# Topsheet.net
KiCad netlist of a schematic drawn in Altium Designer
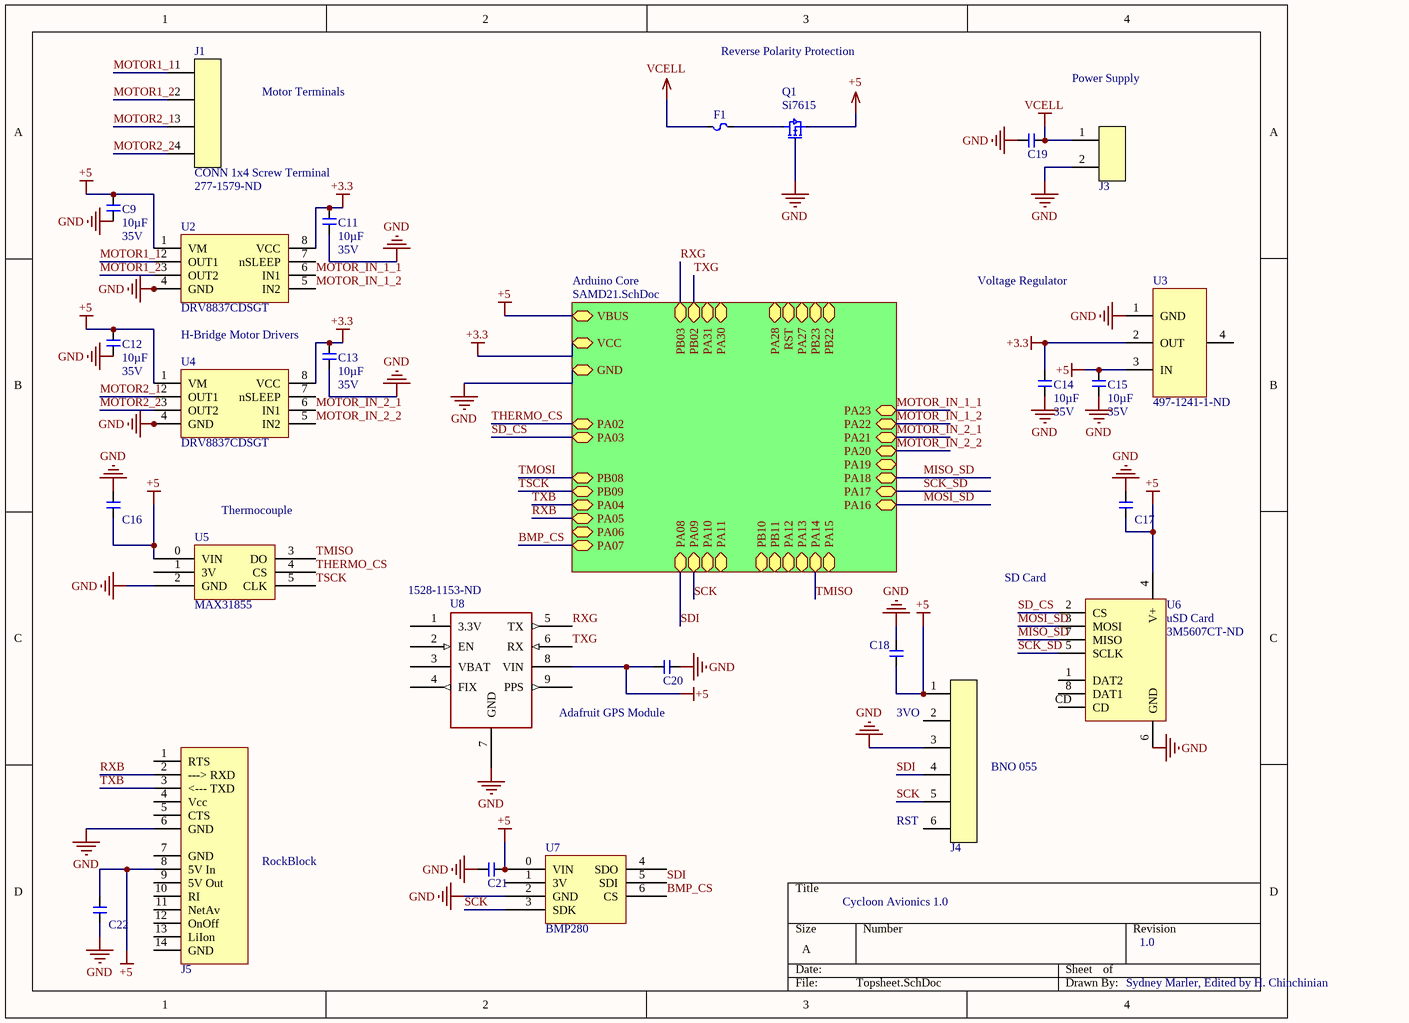
[diagram p0: Topsheet.SchDoc]

(export (version "E")
  (design (tool "Eeschema 10.0.6"))
  (components
    (comp (ref "C9")
      (value "__template_cap")
      (footprint "C0603")
      (description "CAP CER 10UF 35V X5R 0603 20%")
      (fields
        (field (name "CAPACITANCE (SHORTHAND)") "10µF")
        (field (name "RATED VOLTAGE") "35V")
        (field (name "MANUFACTURER") "Murata Electronics North America")
      )
      (libsource (lib "passives") (part "__template_cap"))
    )
    (comp (ref "C11")
      (value "__template_cap")
      (footprint "C0603")
      (description "CAP CER 10UF 35V X5R 0603 20%")
      (fields
        (field (name "CAPACITANCE (SHORTHAND)") "10µF")
        (field (name "RATED VOLTAGE") "35V")
        (field (name "MANUFACTURER") "Murata Electronics North America")
      )
      (libsource (lib "passives") (part "__template_cap"))
    )
    (comp (ref "C12")
      (value "__template_cap")
      (footprint "C0603")
      (description "CAP CER 10UF 35V X5R 0603 20%")
      (fields
        (field (name "CAPACITANCE (SHORTHAND)") "10µF")
        (field (name "RATED VOLTAGE") "35V")
        (field (name "MANUFACTURER") "Murata Electronics North America")
      )
      (libsource (lib "passives") (part "__template_cap"))
    )
    (comp (ref "C13")
      (value "__template_cap")
      (footprint "C0603")
      (description "CAP CER 10UF 35V X5R 0603 20%")
      (fields
        (field (name "CAPACITANCE (SHORTHAND)") "10µF")
        (field (name "RATED VOLTAGE") "35V")
        (field (name "MANUFACTURER") "Murata Electronics North America")
      )
      (libsource (lib "passives") (part "__template_cap"))
    )
    (comp (ref "C14")
      (value "__template_cap")
      (footprint "C0603")
      (description "CAP CER 10UF 35V X5R 0603 20%")
      (fields
        (field (name "CAPACITANCE (SHORTHAND)") "10µF")
        (field (name "RATED VOLTAGE") "35V")
        (field (name "MANUFACTURER") "Murata Electronics North America")
      )
      (libsource (lib "passives") (part "__template_cap"))
    )
    (comp (ref "C15")
      (value "__template_cap")
      (footprint "C0603")
      (description "CAP CER 10UF 35V X5R 0603 20%")
      (fields
        (field (name "CAPACITANCE (SHORTHAND)") "10µF")
        (field (name "RATED VOLTAGE") "35V")
        (field (name "MANUFACTURER") "Murata Electronics North America")
      )
      (libsource (lib "passives") (part "__template_cap"))
    )
    (comp (ref "C16")
      (value "__template_cap")
      (footprint "C0603")
      (libsource (lib "SSI") (part "__template_cap"))
    )
    (comp (ref "C17")
      (value "__template_cap")
      (footprint "C0603")
      (libsource (lib "SSI") (part "__template_cap"))
    )
    (comp (ref "C18")
      (value "__template_cap")
      (footprint "C0603")
      (libsource (lib "SSI") (part "__template_cap"))
    )
    (comp (ref "C19")
      (value "__template_cap")
      (footprint "C0603")
      (libsource (lib "SSI") (part "__template_cap"))
    )
    (comp (ref "C20")
      (value "__template_cap")
      (footprint "C0603")
      (libsource (lib "SSI") (part "__template_cap"))
    )
    (comp (ref "C21")
      (value "__template_cap")
      (footprint "C0603")
      (libsource (lib "SSI") (part "__template_cap"))
    )
    (comp (ref "C22")
      (value "__template_cap")
      (footprint "C0603")
      (libsource (lib "SSI") (part "__template_cap"))
    )
    (comp (ref "F1")
      (value "__template_fuse")
      (footprint "R1206")
      (libsource (lib "Stanford Student Space Initiative") (part "Symbol"))
    )
    (comp (ref "J1")
      (value "CONN 1x4 Screw Terminal")
      (footprint "CONN_1x4_5mm")
      (description "CONN 1x4 Screw Terminal: Phoenix Contact 1935187")
      (fields (field (name "SUPPLIER PART NUMBER 1") "277-1579-ND"))
      (libsource (lib "SSI") (part "CONN_1x4_PhoenixContact_1935187"))
    )
    (comp (ref "J3")
      (value "CONN HEADER 2POS VERT T/H")
      (footprint "CONN_1x2_100MIL")
      (fields (field (name "MANUFACTURER") "FCI") (field (name "MANUFACTURER PART NUMBER") "77311-118-02LF"))
      (libsource (lib "SSI") (part "CONN_1x2"))
    )
    (comp (ref "J4")
      (value "CONN HEADER 6POS T/H")
      (footprint "CONN_1x6_100MIL")
      (libsource (lib "SSI") (part "CONN_1x6"))
    )
    (comp (ref "J5")
      (value "ROCKBLOCK_V2")
      (footprint "ROCKBLOCK_V2")
      (description "CHILD OF SATAN, SOURCE OF BOTH TREMENDOUS FORTUNE AND UNSPEAKABLE ANGUISH")
      (libsource (lib "SSI") (part "ROCKBLOCK_V2"))
    )
    (comp (ref "Q1")
      (value "Si7615")
      (footprint "POWERPAK_1212-8_SINGLE")
      (description "MOSFET P-CH 20V 35A PPK")
      (fields
        (field (name "MANUFACTURER") "Vishay Siliconix")
        (field (name "MANUFACTURER PART NUMBER") "SI7615ADN-T1-GE3")
      )
      (libsource (lib "SSI") (part "PFET_SI7615ADN-T1"))
    )
    (comp (ref "U2")
      (value "DRV8837CDSGT")
      (footprint "8WSON")
      (description "MOTOR DRIVER 1A")
      (fields (field (name "MANUFACTURER") "Texas Instruments"))
      (libsource (lib "SSI") (part "MOTOR_HBRIDGE_DRV8837C"))
    )
    (comp (ref "U3")
      (value "LDO_LD1117S33CTR")
      (footprint "4SOT223")
      (description "IC VOLTAGE REG 3.3V 800MA SOT223 INDUSTRIAL TEMP")
      (fields
        (field (name "MANUFACTURER") "STMicroelectronics")
        (field (name "MANUFACTURER PART NUMBER") "LD1117S33CTR")
        (field (name "SUPPLIER PART NUMBER 1") "497-1241-1-ND")
      )
      (libsource (lib "SSI") (part "LDO_LD1117S33CTR"))
    )
    (comp (ref "U4")
      (value "DRV8837CDSGT")
      (footprint "8WSON")
      (description "MOTOR DRIVER 1A")
      (fields (field (name "MANUFACTURER") "Texas Instruments"))
      (libsource (lib "SSI") (part "MOTOR_HBRIDGE_DRV8837C"))
    )
    (comp (ref "U5")
      (value "MAX31855")
      (footprint "ADAFRUIT_THERMOCOUPLE_BREAKOUT")
      (libsource (lib "SSI") (part "ADAFRUIT_THERMOCOUPLE_BREAKOUT"))
    )
    (comp (ref "U6")
      (value "uSD Card")
      (footprint "MICROSD_CARD_SOCKET")
      (description "MICROSD CARD HOLDER, PUSH-PUSH")
      (fields
        (field (name "MANUFACTURER") "3M")
        (field (name "MANUFACTURER PART NUMBER") "2908-05WB-MG")
        (field (name "SUPPLIER PART NUMBER 1") "3M5607CT-ND")
      )
      (libsource (lib "SSI") (part "MICRO_SD_CARD_HOLDER"))
    )
    (comp (ref "U7")
      (value "BMP280")
      (footprint "ADAFRUIT_BMP280_BREAKOUT")
      (libsource (lib "SSI") (part "ADAFRUIT_BMP280_BREAKOUT"))
    )
    (comp (ref "U8")
      (value "Adafruit GPS Module")
      (footprint "adafruit_gps_746")
      (description "https://www.adafruit.com/product/746")
      (fields (field (name "SUPPLIER PART NUMBER 1") "1528-1153-ND"))
      (libsource (lib "modules") (part "ADAFRUIT_GPS_746"))
    )
  )
  (nets
    (net (code "1") (name "+3.3") (class "Default")
      (node (ref "C11") (pin "1") (pintype "passive"))
      (node (ref "C13") (pin "1") (pintype "passive"))
      (node (ref "C14") (pin "1") (pintype "passive"))
      (node (ref "U2") (pin "8") (pinfunction "VCC_8") (pintype "passive"))
      (node (ref "U3") (pin "2") (pinfunction "OUT_2") (pintype "passive"))
      (node (ref "U4") (pin "8") (pinfunction "VCC_8") (pintype "passive"))
    )
    (net (code "2") (name "+5") (class "Default")
      (node (ref "C12") (pin "1") (pintype "passive"))
      (node (ref "C15") (pin "1") (pintype "passive"))
      (node (ref "C16") (pin "2") (pintype "passive"))
      (node (ref "C17") (pin "2") (pintype "passive"))
      (node (ref "C18") (pin "2") (pintype "passive"))
      (node (ref "C20") (pin "1") (pintype "passive"))
      (node (ref "C21") (pin "2") (pintype "passive"))
      (node (ref "C22") (pin "1") (pintype "passive"))
      (node (ref "C9") (pin "1") (pintype "passive"))
      (node (ref "J4") (pin "1") (pinfunction "1_1") (pintype "passive"))
      (node (ref "J5") (pin "8") (pinfunction "5V_In_8") (pintype "passive"))
      (node (ref "Q1") (pin "2") (pintype "passive"))
      (node (ref "U2") (pin "1") (pinfunction "VM_1") (pintype "passive"))
      (node (ref "U3") (pin "3") (pinfunction "IN_3") (pintype "passive"))
      (node (ref "U4") (pin "1") (pinfunction "VM_1") (pintype "passive"))
      (node (ref "U5") (pin "0") (pinfunction "VIN_0") (pintype "passive"))
      (node (ref "U6") (pin "4") (pinfunction "V+_4") (pintype "passive"))
      (node (ref "U7") (pin "0") (pinfunction "VIN_0") (pintype "passive"))
      (node (ref "U8") (pin "8") (pinfunction "VIN_8") (pintype "power_in"))
    )
    (net (code "3") (name "/BMP_CS") (class "Default")
      (node (ref "U7") (pin "6") (pinfunction "CS_6") (pintype "passive"))
    )
    (net (code "4") (name "/MISO_SD") (class "Default")
      (node (ref "U6") (pin "7") (pinfunction "MISO_7") (pintype "passive"))
    )
    (net (code "5") (name "/MOSI_SD") (class "Default")
      (node (ref "U6") (pin "3") (pinfunction "MOSI_3") (pintype "passive"))
    )
    (net (code "6") (name "/MOTOR1_1") (class "Default")
      (node (ref "J1") (pin "1") (pinfunction "1_1") (pintype "passive"))
      (node (ref "U2") (pin "2") (pinfunction "OUT1_2") (pintype "passive"))
    )
    (net (code "7") (name "/MOTOR1_2") (class "Default")
      (node (ref "J1") (pin "2") (pinfunction "2_2") (pintype "passive"))
      (node (ref "U2") (pin "3") (pinfunction "OUT2_3") (pintype "passive"))
    )
    (net (code "8") (name "/MOTOR2_1") (class "Default")
      (node (ref "J1") (pin "3") (pinfunction "3_3") (pintype "passive"))
      (node (ref "U4") (pin "2") (pinfunction "OUT1_2") (pintype "passive"))
    )
    (net (code "9") (name "/MOTOR2_2") (class "Default")
      (node (ref "J1") (pin "4") (pinfunction "4_4") (pintype "passive"))
      (node (ref "U4") (pin "3") (pinfunction "OUT2_3") (pintype "passive"))
    )
    (net (code "10") (name "/MOTOR_IN_1_1") (class "Default")
      (node (ref "U2") (pin "6") (pinfunction "IN1_6") (pintype "passive"))
    )
    (net (code "11") (name "/MOTOR_IN_1_2") (class "Default")
      (node (ref "U2") (pin "5") (pinfunction "IN2_5") (pintype "passive"))
    )
    (net (code "12") (name "/MOTOR_IN_2_1") (class "Default")
      (node (ref "U4") (pin "6") (pinfunction "IN1_6") (pintype "passive"))
    )
    (net (code "13") (name "/MOTOR_IN_2_2") (class "Default")
      (node (ref "U4") (pin "5") (pinfunction "IN2_5") (pintype "passive"))
    )
    (net (code "30") (name "/RXB") (class "Default")
      (node (ref "J5") (pin "2") (pinfunction "--->_RXD_2") (pintype "passive"))
    )
    (net (code "31") (name "/RXG") (class "Default")
      (node (ref "U8") (pin "5") (pinfunction "TX_5") (pintype "output"))
    )
    (net (code "32") (name "/SCK") (class "Default")
      (node (ref "J4") (pin "5") (pinfunction "5_5") (pintype "passive"))
      (node (ref "U7") (pin "3") (pinfunction "SDK_3") (pintype "passive"))
    )
    (net (code "33") (name "/SCK_SD") (class "Default")
      (node (ref "U6") (pin "5") (pinfunction "SCLK_5") (pintype "passive"))
    )
    (net (code "34") (name "/SDI") (class "Default")
      (node (ref "J4") (pin "4") (pinfunction "4_4") (pintype "passive"))
      (node (ref "U7") (pin "5") (pinfunction "SDI_5") (pintype "passive"))
    )
    (net (code "35") (name "/SD_CS") (class "Default")
      (node (ref "U6") (pin "2") (pinfunction "CS_2") (pintype "passive"))
    )
    (net (code "36") (name "/THERMO_CS") (class "Default")
      (node (ref "U5") (pin "4") (pinfunction "CS_4") (pintype "passive"))
    )
    (net (code "37") (name "/TMISO") (class "Default")
      (node (ref "U5") (pin "3") (pinfunction "DO_3") (pintype "passive"))
    )
    (net (code "39") (name "/TSCK") (class "Default")
      (node (ref "U5") (pin "5") (pinfunction "CLK_5") (pintype "passive"))
    )
    (net (code "40") (name "/TXB") (class "Default")
      (node (ref "J5") (pin "3") (pinfunction "<---_TXD_3") (pintype "passive"))
    )
    (net (code "41") (name "/TXG") (class "Default")
      (node (ref "U8") (pin "6") (pinfunction "RX_6") (pintype "input"))
    )
    (net (code "42") (name "GND") (class "Default")
      (node (ref "C11") (pin "2") (pintype "passive"))
      (node (ref "C12") (pin "2") (pintype "passive"))
      (node (ref "C13") (pin "2") (pintype "passive"))
      (node (ref "C14") (pin "2") (pintype "passive"))
      (node (ref "C15") (pin "2") (pintype "passive"))
      (node (ref "C16") (pin "1") (pintype "passive"))
      (node (ref "C17") (pin "1") (pintype "passive"))
      (node (ref "C18") (pin "1") (pintype "passive"))
      (node (ref "C19") (pin "1") (pintype "passive"))
      (node (ref "C20") (pin "2") (pintype "passive"))
      (node (ref "C21") (pin "1") (pintype "passive"))
      (node (ref "C22") (pin "2") (pintype "passive"))
      (node (ref "C9") (pin "2") (pintype "passive"))
      (node (ref "J3") (pin "2") (pinfunction "2_2") (pintype "passive"))
      (node (ref "J4") (pin "3") (pinfunction "3_3") (pintype "passive"))
      (node (ref "J5") (pin "6") (pinfunction "GND_6") (pintype "passive"))
      (node (ref "Q1") (pin "1") (pintype "passive"))
      (node (ref "U2") (pin "4") (pinfunction "GND_4") (pintype "passive"))
      (node (ref "U2") (pin "PAD") (pinfunction "PAD_PAD") (pintype "passive"))
      (node (ref "U3") (pin "1") (pinfunction "GND_1") (pintype "passive"))
      (node (ref "U4") (pin "4") (pinfunction "GND_4") (pintype "passive"))
      (node (ref "U4") (pin "PAD") (pinfunction "PAD_PAD") (pintype "passive"))
      (node (ref "U5") (pin "2") (pinfunction "GND_2") (pintype "passive"))
      (node (ref "U6") (pin "6") (pinfunction "GND_6") (pintype "passive"))
      (node (ref "U7") (pin "2") (pinfunction "GND_2") (pintype "passive"))
      (node (ref "U8") (pin "7") (pinfunction "GND_7") (pintype "power_in"))
    )
    (net (code "43") (name "Net-(F1-Pad2)") (class "Default")
      (node (ref "F1") (pin "2") (pintype "passive"))
      (node (ref "Q1") (pin "3") (pintype "passive"))
    )
    (net (code "44") (name "VCELL") (class "Default")
      (node (ref "C19") (pin "2") (pintype "passive"))
      (node (ref "F1") (pin "1") (pintype "passive"))
      (node (ref "J3") (pin "1") (pinfunction "1_1") (pintype "passive"))
    )
    (net (code "45") (name "unconnected-(J4-Pad2)") (class "Default")
      (node (ref "J4") (pin "2") (pinfunction "2_2") (pintype "passive"))
    )
    (net (code "46") (name "unconnected-(J4-Pad6)") (class "Default")
      (node (ref "J4") (pin "6") (pinfunction "6_6") (pintype "passive"))
    )
    (net (code "47") (name "unconnected-(J5-5V_Out-Pad9)") (class "Default")
      (node (ref "J5") (pin "9") (pinfunction "5V_Out_9") (pintype "passive"))
    )
    (net (code "48") (name "unconnected-(J5-CTS-Pad5)") (class "Default")
      (node (ref "J5") (pin "5") (pinfunction "CTS_5") (pintype "passive"))
    )
    (net (code "49") (name "unconnected-(J5-GND-Pad7)") (class "Default")
      (node (ref "J5") (pin "7") (pinfunction "GND_7") (pintype "passive"))
    )
    (net (code "50") (name "unconnected-(J5-GND-Pad14)") (class "Default")
      (node (ref "J5") (pin "14") (pinfunction "GND_14") (pintype "passive"))
    )
    (net (code "51") (name "unconnected-(J5-LiIon-Pad13)") (class "Default")
      (node (ref "J5") (pin "13") (pinfunction "LiIon_13") (pintype "passive"))
    )
    (net (code "52") (name "unconnected-(J5-NetAv-Pad11)") (class "Default")
      (node (ref "J5") (pin "11") (pinfunction "NetAv_11") (pintype "passive"))
    )
    (net (code "53") (name "unconnected-(J5-OnOff-Pad12)") (class "Default")
      (node (ref "J5") (pin "12") (pinfunction "OnOff_12") (pintype "passive"))
    )
    (net (code "54") (name "unconnected-(J5-RI-Pad10)") (class "Default")
      (node (ref "J5") (pin "10") (pinfunction "RI_10") (pintype "passive"))
    )
    (net (code "55") (name "unconnected-(J5-RTS-Pad1)") (class "Default")
      (node (ref "J5") (pin "1") (pinfunction "RTS_1") (pintype "passive"))
    )
    (net (code "56") (name "unconnected-(J5-Vcc-Pad4)") (class "Default")
      (node (ref "J5") (pin "4") (pinfunction "Vcc_4") (pintype "passive"))
    )
    (net (code "57") (name "unconnected-(U2-nSLEEP-Pad7)") (class "Default")
      (node (ref "U2") (pin "7") (pinfunction "nSLEEP_7") (pintype "passive"))
    )
    (net (code "58") (name "unconnected-(U3-GND-Pad4)") (class "Default")
      (node (ref "U3") (pin "4") (pinfunction "GND_4") (pintype "passive"))
    )
    (net (code "59") (name "unconnected-(U4-nSLEEP-Pad7)") (class "Default")
      (node (ref "U4") (pin "7") (pinfunction "nSLEEP_7") (pintype "passive"))
    )
    (net (code "60") (name "unconnected-(U5-3V-Pad1)") (class "Default")
      (node (ref "U5") (pin "1") (pinfunction "3V_1") (pintype "passive"))
    )
    (net (code "61") (name "unconnected-(U6-DAT1-Pad8)") (class "Default")
      (node (ref "U6") (pin "8") (pinfunction "DAT1_8") (pintype "passive"))
    )
    (net (code "62") (name "unconnected-(U6-DAT2-Pad1)") (class "Default")
      (node (ref "U6") (pin "1") (pinfunction "DAT2_1") (pintype "passive"))
    )
    (net (code "63") (name "unconnected-(U6-PadCD)") (class "Default")
      (node (ref "U6") (pin "CD") (pinfunction "CD_CD") (pintype "passive"))
    )
    (net (code "64") (name "unconnected-(U7-3V-Pad1)") (class "Default")
      (node (ref "U7") (pin "1") (pinfunction "3V_1") (pintype "passive"))
    )
    (net (code "65") (name "unconnected-(U7-SDO-Pad4)") (class "Default")
      (node (ref "U7") (pin "4") (pinfunction "SDO_4") (pintype "passive"))
    )
    (net (code "66") (name "unconnected-(U8-3.3V-Pad1)") (class "Default")
      (node (ref "U8") (pin "1") (pinfunction "3.3V_1") (pintype "power_in"))
    )
    (net (code "67") (name "unconnected-(U8-EN-Pad2)") (class "Default")
      (node (ref "U8") (pin "2") (pinfunction "EN_2") (pintype "input"))
    )
    (net (code "68") (name "unconnected-(U8-FIX-Pad4)") (class "Default")
      (node (ref "U8") (pin "4") (pinfunction "FIX_4") (pintype "output"))
    )
    (net (code "69") (name "unconnected-(U8-PPS-Pad9)") (class "Default")
      (node (ref "U8") (pin "9") (pinfunction "PPS_9") (pintype "output"))
    )
    (net (code "70") (name "unconnected-(U8-VBAT-Pad3)") (class "Default")
      (node (ref "U8") (pin "3") (pinfunction "VBAT_3") (pintype "power_in"))
    )
  )
)
